# Encoder.net
KiCad netlist of a schematic drawn in Altium Designer
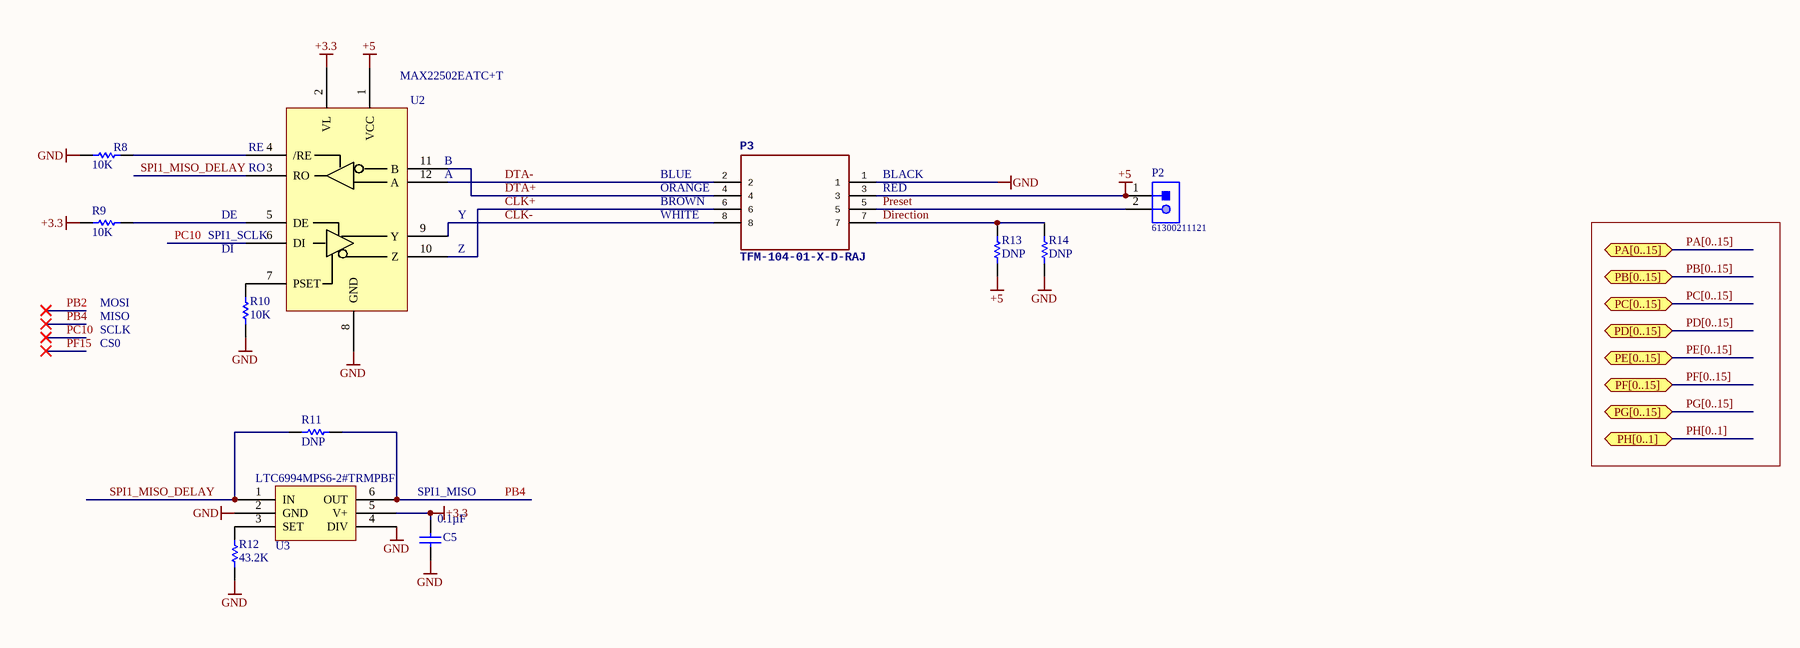
[diagram p0: Encoder.SchDoc]

(export (version "E")
  (design (tool "Eeschema 10.0.6"))
  (components
    (comp (ref "C5")
      (value "CAP CER 0.1UF 25V X7R 0805")
      (footprint "CAPC0805(2012)145_N")
      (fields
        (field (name "MANUFACTURER") "Murata Electronics North America")
        (field (name "MANUFACTURER PART NUMBER") "GRM21BR71E104KA01L")
        (field (name "CAPACITANCE") "0.1µF")
        (field (name "TOLERANCE") "±10%")
      )
      (libsource (lib "Altium Content Vault") (part "CMP-1036-04795-1"))
    )
    (comp (ref "P2")
      (value "61300211121")
      (footprint "61300211121")
      (description "THT Vertical Pin Header WR-PHD, Pitch 2.54 mm, Single Row, 2 pins")
      (fields (field (name "MANUFACTURER") "Wurth Elektronik") (field (name "PUBLISHER") "WurthElektronik"))
      (libsource (lib "Altium Content Vault") (part "WE-CN-1P-M-R2"))
    )
    (comp (ref "P3")
      (value "TFM-104-01-X-D-RAJ")
      (footprint "SAMTEC-TFM-104-01-X-D-RA")
      (fields (field (name "MANUFACTURER") "SAMTEC"))
      (libsource (lib "SAMTEC-TFM-104-01-X-D-RA") (part "SAMTEC-TFM-104-01-X-D-RAJ"))
    )
    (comp (ref "R8")
      (value "10K")
      (footprint "RESC0805(2012)_L")
      (description "RES SMD 10K OHM 1% 1/8W 0805")
      (fields
        (field (name "MANUFACTURER") "Vishay Dale")
        (field (name "MANUFACTURER PART NUMBER") "CRCW080510K0FKEA")
      )
      (libsource (lib "Altium Content Vault") (part "CMP-1013-00215-1"))
    )
    (comp (ref "R9")
      (value "10K")
      (footprint "RESC0805(2012)_L")
      (description "RES SMD 10K OHM 1% 1/8W 0805")
      (fields
        (field (name "MANUFACTURER") "Vishay Dale")
        (field (name "MANUFACTURER PART NUMBER") "CRCW080510K0FKEA")
      )
      (libsource (lib "Altium Content Vault") (part "CMP-1013-00215-1"))
    )
    (comp (ref "R10")
      (value "10K")
      (footprint "RESC0805(2012)_L")
      (description "RES SMD 10K OHM 1% 1/8W 0805")
      (fields
        (field (name "MANUFACTURER") "Vishay Dale")
        (field (name "MANUFACTURER PART NUMBER") "CRCW080510K0FKEA")
      )
      (libsource (lib "Altium Content Vault") (part "CMP-1013-00215-1"))
    )
    (comp (ref "R11")
      (value "DNP")
      (footprint "RESC0805(2012)_L")
      (description "RES SMD 0 OHM 5% 1/8W 0805")
      (fields
        (field (name "MANUFACTURER") "Vishay")
        (field (name "MANUFACTURER PART NUMBER") "CRCW08050000Z0EA")
      )
      (libsource (lib "Altium Content Vault") (part "CMP-1013-00215-1"))
    )
    (comp (ref "R12")
      (value "43.2K")
      (footprint "RESC0805(2012)_L")
      (description "RES SMD 43.2K OHM 1% 1/8W 0805")
      (fields
        (field (name "MANUFACTURER") "Vishay Dale")
        (field (name "MANUFACTURER PART NUMBER") "CRCW080543K2FKEA")
      )
      (libsource (lib "Altium Content Vault") (part "CMP-1013-00215-1"))
    )
    (comp (ref "R13")
      (value "DNP")
      (footprint "RESC0805(2012)_L")
      (description "RES SMD 0 OHM 5% 1/8W 0805")
      (libsource (lib "Altium Content Vault") (part "CMP-1013-00215-1"))
    )
    (comp (ref "R14")
      (value "DNP")
      (footprint "RESC0805(2012)_L")
      (description "RES SMD 0 OHM 5% 1/8W 0805")
      (libsource (lib "Altium Content Vault") (part "CMP-1013-00215-1"))
    )
    (comp (ref "U2")
      (value "MAX22502EATC+T")
      (footprint "MAX22502EATC+T")
      (description "PLANAR E CORES")
      (fields (field (name "MANUFACTURER") "Maxim"))
      (libsource (lib "ZLS_Schematic_lib") (part "MAX22502EATC+T"))
    )
    (comp (ref "U3")
      (value "LTC6994MPS6-2#TRMPBF")
      (footprint "LTC6994MPS6-2#TRMPBF")
      (description "IC DELAY BLOCK 8TAP PROG TSOT23")
      (fields
        (field (name "MANUFACTURER") "Linear Technology/Analog Devices")
        (field (name "MANUFACTURER PART NUMBER") "LTC6994CS6-2#TRMPBF")
      )
      (libsource (lib "ZLS_Schematic_lib") (part "LTC6994MPS6-2#TRMPBF"))
    )
  )
  (nets
    (net (code "111") (name "+3.3") (class "Default")
      (node (ref "C5") (pin "1") (pinfunction "1_1") (pintype "passive"))
      (node (ref "R9") (pin "2") (pinfunction "2_2") (pintype "passive"))
      (node (ref "U2") (pin "2") (pinfunction "VL_2") (pintype "passive"))
      (node (ref "U3") (pin "5") (pinfunction "V+_5") (pintype "passive"))
    )
    (net (code "112") (name "+5") (class "Default")
      (node (ref "P2") (pin "1") (pinfunction "1_1") (pintype "passive"))
      (node (ref "P3") (pin "3") (pinfunction "3_3") (pintype "passive"))
      (node (ref "R13") (pin "1") (pinfunction "1_1") (pintype "passive"))
      (node (ref "U2") (pin "1") (pinfunction "VCC_1") (pintype "passive"))
    )
    (net (code "113") (name "/CLK+") (class "Default")
      (node (ref "P3") (pin "6") (pinfunction "6_6") (pintype "passive"))
      (node (ref "U2") (pin "10") (pinfunction "Z_10") (pintype "passive"))
    )
    (net (code "114") (name "/CLK-") (class "Default")
      (node (ref "P3") (pin "8") (pinfunction "8_8") (pintype "passive"))
      (node (ref "U2") (pin "9") (pinfunction "Y_9") (pintype "passive"))
    )
    (net (code "115") (name "/DTA+") (class "Default")
      (node (ref "P3") (pin "4") (pinfunction "4_4") (pintype "passive"))
      (node (ref "U2") (pin "11") (pinfunction "B_11") (pintype "passive"))
    )
    (net (code "116") (name "/DTA-") (class "Default")
      (node (ref "P3") (pin "2") (pinfunction "2_2") (pintype "passive"))
      (node (ref "U2") (pin "12") (pinfunction "A_12") (pintype "passive"))
    )
    (net (code "117") (name "/Direction") (class "Default")
      (node (ref "P3") (pin "7") (pinfunction "7_7") (pintype "passive"))
      (node (ref "R13") (pin "2") (pinfunction "2_2") (pintype "passive"))
      (node (ref "R14") (pin "2") (pinfunction "2_2") (pintype "passive"))
    )
    (net (code "120") (name "/PB4") (class "Default")
      (node (ref "R11") (pin "2") (pinfunction "2_2") (pintype "passive"))
      (node (ref "U3") (pin "6") (pinfunction "OUT_6") (pintype "passive"))
    )
    (net (code "122") (name "/PC10") (class "Default")
      (node (ref "U2") (pin "6") (pinfunction "DI_6") (pintype "passive"))
    )
    (net (code "130") (name "/Preset") (class "Default")
      (node (ref "P2") (pin "2") (pinfunction "2_2") (pintype "passive"))
      (node (ref "P3") (pin "5") (pinfunction "5_5") (pintype "passive"))
    )
    (net (code "131") (name "/SPI1_MISO_DELAY") (class "Default")
      (node (ref "R11") (pin "1") (pinfunction "1_1") (pintype "passive"))
      (node (ref "U2") (pin "3") (pinfunction "RO_3") (pintype "passive"))
      (node (ref "U3") (pin "1") (pinfunction "IN_1") (pintype "passive"))
    )
    (net (code "132") (name "GND") (class "Default")
      (node (ref "C5") (pin "2") (pinfunction "2_2") (pintype "passive"))
      (node (ref "P3") (pin "1") (pinfunction "1_1") (pintype "passive"))
      (node (ref "R10") (pin "2") (pinfunction "2_2") (pintype "passive"))
      (node (ref "R12") (pin "2") (pinfunction "2_2") (pintype "passive"))
      (node (ref "R14") (pin "1") (pinfunction "1_1") (pintype "passive"))
      (node (ref "R8") (pin "2") (pinfunction "2_2") (pintype "passive"))
      (node (ref "U2") (pin "8") (pinfunction "GND_8") (pintype "passive"))
      (node (ref "U3") (pin "2") (pinfunction "GND_2") (pintype "passive"))
      (node (ref "U3") (pin "4") (pinfunction "DIV_4") (pintype "passive"))
    )
    (net (code "133") (name "Net-(U2-DE)") (class "Default")
      (node (ref "R9") (pin "1") (pinfunction "1_1") (pintype "passive"))
      (node (ref "U2") (pin "5") (pinfunction "DE_5") (pintype "passive"))
    )
    (net (code "134") (name "Net-(U2-PSET)") (class "Default")
      (node (ref "R10") (pin "1") (pinfunction "1_1") (pintype "passive"))
      (node (ref "U2") (pin "7") (pinfunction "PSET_7") (pintype "passive"))
    )
    (net (code "135") (name "Net-(U2-{slash}RE)") (class "Default")
      (node (ref "R8") (pin "1") (pinfunction "1_1") (pintype "passive"))
      (node (ref "U2") (pin "4") (pinfunction "/RE_4") (pintype "passive"))
    )
    (net (code "136") (name "Net-(U3-SET)") (class "Default")
      (node (ref "R12") (pin "1") (pinfunction "1_1") (pintype "passive"))
      (node (ref "U3") (pin "3") (pinfunction "SET_3") (pintype "passive"))
    )
  )
)
